# Tip_Tilt_Controller.net
KiCad netlist of a schematic drawn in EAGLE
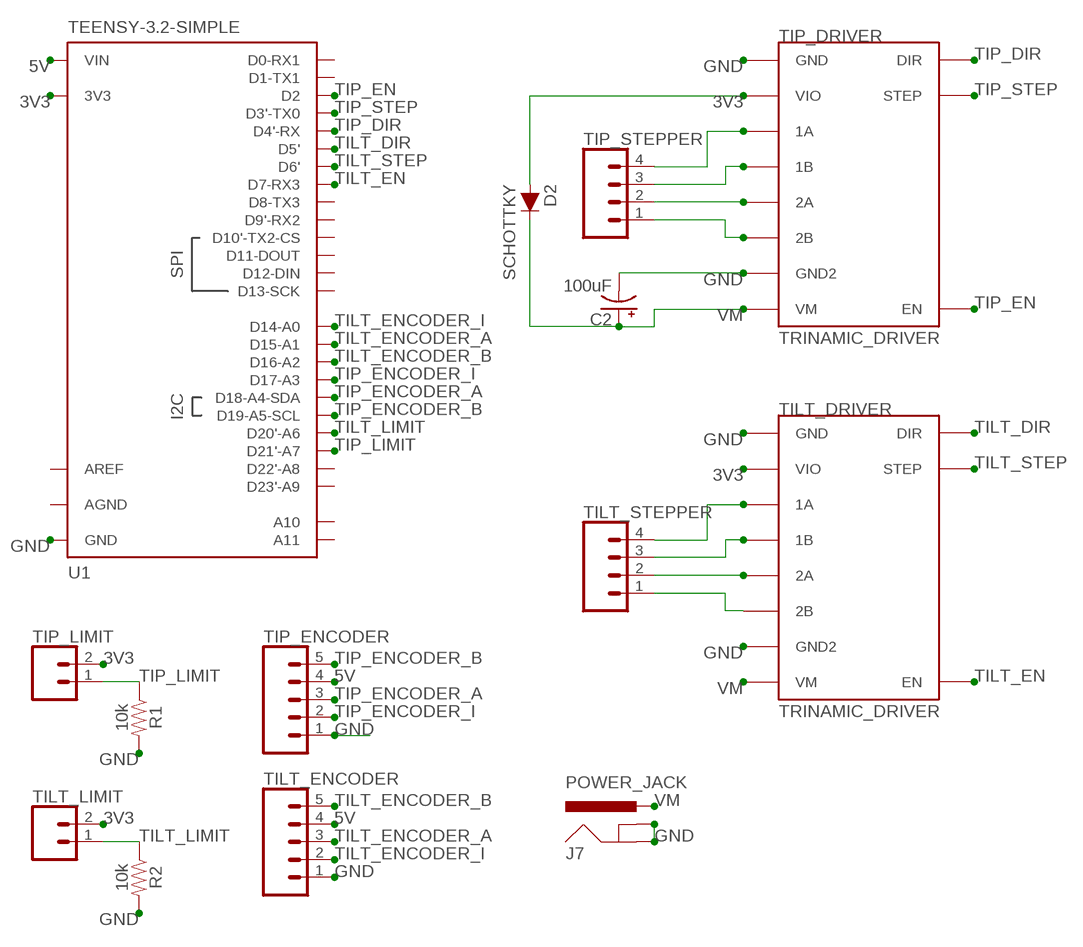
[diagram p0: schematic, sheet 1]

(export (version "E")
  (design (tool "Eeschema 10.0.6"))
  (components
    (comp (ref "C2")
      (value "100uF")
      (footprint "eagle-import:CPOL-RADIAL-2.5MM-6.5MM")
      (libsource (lib "eagle-import") (part "100UF-POLAR-RADIAL-2.5MM-25V-20%"))
    )
    (comp (ref "D2")
      (value "SCHOTTKY")
      (footprint "eagle-import:DIODE-1N4148")
      (libsource (lib "eagle-import") (part "DIODE-1N4148"))
    )
    (comp (ref "J7")
      (value "POWER_JACK")
      (footprint "eagle-import:POWER_JACK_PTH")
      (libsource (lib "eagle-import") (part "POWER_JACK"))
    )
    (comp (ref "R1")
      (value "10k")
      (footprint "eagle-import:AXIAL-0.3")
      (libsource (lib "eagle-import") (part "10KOHM-HORIZ-1/6W-5%"))
    )
    (comp (ref "R2")
      (value "10k")
      (footprint "eagle-import:AXIAL-0.3")
      (libsource (lib "eagle-import") (part "10KOHM-HORIZ-1/6W-5%"))
    )
    (comp (ref "TILT_DRIVER")
      (value "TRINAMIC_DRIVER")
      (footprint "eagle-import:TRINAMIC_DRIVER")
      (libsource (lib "eagle-import") (part "TRINAMIC_DRIVER"))
    )
    (comp (ref "TILT_ENCODER")
      (value "CONN_05")
      (footprint "eagle-import:1X05")
      (libsource (lib "eagle-import") (part "CONN_05"))
    )
    (comp (ref "TILT_LIMIT")
      (value "CONN_02")
      (footprint "eagle-import:1X02")
      (libsource (lib "eagle-import") (part "CONN_02"))
    )
    (comp (ref "TILT_STEPPER")
      (value "CONN_04PTH")
      (footprint "eagle-import:1X04")
      (libsource (lib "eagle-import") (part "CONN_04PTH"))
    )
    (comp (ref "TIP_DRIVER")
      (value "TRINAMIC_DRIVER")
      (footprint "eagle-import:TRINAMIC_DRIVER")
      (libsource (lib "eagle-import") (part "TRINAMIC_DRIVER"))
    )
    (comp (ref "TIP_ENCODER")
      (value "CONN_05")
      (footprint "eagle-import:1X05")
      (libsource (lib "eagle-import") (part "CONN_05"))
    )
    (comp (ref "TIP_LIMIT")
      (value "CONN_02")
      (footprint "eagle-import:1X02")
      (libsource (lib "eagle-import") (part "CONN_02"))
    )
    (comp (ref "TIP_STEPPER")
      (value "CONN_04PTH")
      (footprint "eagle-import:1X04")
      (libsource (lib "eagle-import") (part "CONN_04PTH"))
    )
    (comp (ref "U1")
      (value "TEENSY-3.2-SIMPLE")
      (footprint "eagle-import:TEENSY-3.2-SIMPLE")
      (libsource (lib "eagle-import") (part "TEENSY-3.2-SIMPLE"))
    )
  )
  (nets
    (net (code "1") (name "/3V3") (class "Default")
      (node (ref "D2") (pin "A") (pinfunction "A_A") (pintype "passive"))
      (node (ref "TILT_DRIVER") (pin "5V") (pinfunction "VIO_5V") (pintype "bidirectional"))
      (node (ref "TILT_LIMIT") (pin "2") (pinfunction "2_2") (pintype "passive"))
      (node (ref "TIP_DRIVER") (pin "5V") (pinfunction "VIO_5V") (pintype "bidirectional"))
      (node (ref "TIP_LIMIT") (pin "2") (pinfunction "2_2") (pintype "passive"))
      (node (ref "U1") (pin "3.3V") (pinfunction "3V3_3.3V") (pintype "power_in"))
    )
    (net (code "2") (name "/5V") (class "Default")
      (node (ref "TILT_ENCODER") (pin "4") (pinfunction "4_4") (pintype "passive"))
      (node (ref "TIP_ENCODER") (pin "4") (pinfunction "4_4") (pintype "passive"))
      (node (ref "U1") (pin "VIN") (pinfunction "VIN_VIN") (pintype "power_in"))
    )
    (net (code "3") (name "/AGND") (class "Default")
      (node (ref "U1") (pin "AGND") (pinfunction "AGND_AGND") (pintype "power_in"))
    )
    (net (code "4") (name "/AREF") (class "Default")
      (node (ref "U1") (pin "AREF") (pinfunction "AREF_AREF") (pintype "power_in"))
    )
    (net (code "5") (name "/GND") (class "Default")
      (node (ref "C2") (pin "2") (pinfunction "-_2") (pintype "passive"))
      (node (ref "J7") (pin "GND") (pinfunction "GND_GND") (pintype "bidirectional"))
      (node (ref "J7") (pin "GNDBREAK") (pinfunction "GNDBREAK_GNDBREAK") (pintype "bidirectional"))
      (node (ref "R1") (pin "P$2") (pinfunction "2_P$2") (pintype "passive"))
      (node (ref "R2") (pin "P$2") (pinfunction "2_P$2") (pintype "passive"))
      (node (ref "TILT_DRIVER") (pin "GND") (pinfunction "GND_GND") (pintype "bidirectional"))
      (node (ref "TILT_DRIVER") (pin "GND2") (pinfunction "GND2_GND2") (pintype "bidirectional"))
      (node (ref "TILT_ENCODER") (pin "1") (pinfunction "1_1") (pintype "passive"))
      (node (ref "TIP_DRIVER") (pin "GND") (pinfunction "GND_GND") (pintype "bidirectional"))
      (node (ref "TIP_DRIVER") (pin "GND2") (pinfunction "GND2_GND2") (pintype "bidirectional"))
      (node (ref "TIP_ENCODER") (pin "1") (pinfunction "1_1") (pintype "passive"))
      (node (ref "U1") (pin "GND") (pinfunction "GND_GND") (pintype "power_in"))
    )
    (net (code "6") (name "/TILT_DIR") (class "Default")
      (node (ref "TILT_DRIVER") (pin "DIR") (pinfunction "DIR_DIR") (pintype "bidirectional"))
      (node (ref "U1") (pin "5") (pinfunction "D5'_5") (pintype "bidirectional"))
    )
    (net (code "7") (name "/TILT_EN") (class "Default")
      (node (ref "TILT_DRIVER") (pin "EN") (pinfunction "EN_EN") (pintype "bidirectional"))
      (node (ref "U1") (pin "7") (pinfunction "D7-RX3_7") (pintype "bidirectional"))
    )
    (net (code "8") (name "/TILT_ENCODER_A") (class "Default")
      (node (ref "TILT_ENCODER") (pin "3") (pinfunction "3_3") (pintype "passive"))
      (node (ref "U1") (pin "15") (pinfunction "D15-A1_15") (pintype "bidirectional"))
    )
    (net (code "9") (name "/TILT_ENCODER_B") (class "Default")
      (node (ref "TILT_ENCODER") (pin "5") (pinfunction "5_5") (pintype "passive"))
      (node (ref "U1") (pin "16") (pinfunction "D16-A2_16") (pintype "bidirectional"))
    )
    (net (code "10") (name "/TILT_ENCODER_I") (class "Default")
      (node (ref "TILT_ENCODER") (pin "2") (pinfunction "2_2") (pintype "passive"))
      (node (ref "U1") (pin "14") (pinfunction "D14-A0_14") (pintype "bidirectional"))
    )
    (net (code "11") (name "/TILT_LIMIT") (class "Default")
      (node (ref "R2") (pin "P$1") (pinfunction "1_P$1") (pintype "passive"))
      (node (ref "TILT_LIMIT") (pin "1") (pinfunction "1_1") (pintype "passive"))
      (node (ref "U1") (pin "20") (pinfunction "D20'-A6_20") (pintype "bidirectional"))
    )
    (net (code "12") (name "/TILT_STEP") (class "Default")
      (node (ref "TILT_DRIVER") (pin "STEP") (pinfunction "STEP_STEP") (pintype "bidirectional"))
      (node (ref "U1") (pin "6") (pinfunction "D6'_6") (pintype "bidirectional"))
    )
    (net (code "13") (name "/TIP_DIR") (class "Default")
      (node (ref "TIP_DRIVER") (pin "DIR") (pinfunction "DIR_DIR") (pintype "bidirectional"))
      (node (ref "U1") (pin "4") (pinfunction "D4'-RX_4") (pintype "bidirectional"))
    )
    (net (code "14") (name "/TIP_EN") (class "Default")
      (node (ref "TIP_DRIVER") (pin "EN") (pinfunction "EN_EN") (pintype "bidirectional"))
      (node (ref "U1") (pin "2") (pinfunction "D2_2") (pintype "bidirectional"))
    )
    (net (code "15") (name "/TIP_ENCODER_A") (class "Default")
      (node (ref "TIP_ENCODER") (pin "3") (pinfunction "3_3") (pintype "passive"))
      (node (ref "U1") (pin "18") (pinfunction "D18-A4-SDA_18") (pintype "bidirectional"))
    )
    (net (code "16") (name "/TIP_ENCODER_B") (class "Default")
      (node (ref "TIP_ENCODER") (pin "5") (pinfunction "5_5") (pintype "passive"))
      (node (ref "U1") (pin "19") (pinfunction "D19-A5-SCL_19") (pintype "bidirectional"))
    )
    (net (code "17") (name "/TIP_ENCODER_I") (class "Default")
      (node (ref "TIP_ENCODER") (pin "2") (pinfunction "2_2") (pintype "passive"))
      (node (ref "U1") (pin "17") (pinfunction "D17-A3_17") (pintype "bidirectional"))
    )
    (net (code "18") (name "/TIP_LIMIT") (class "Default")
      (node (ref "R1") (pin "P$1") (pinfunction "1_P$1") (pintype "passive"))
      (node (ref "TIP_LIMIT") (pin "1") (pinfunction "1_1") (pintype "passive"))
      (node (ref "U1") (pin "21") (pinfunction "D21'-A7_21") (pintype "bidirectional"))
    )
    (net (code "19") (name "/TIP_STEP") (class "Default")
      (node (ref "TIP_DRIVER") (pin "STEP") (pinfunction "STEP_STEP") (pintype "bidirectional"))
      (node (ref "U1") (pin "3") (pinfunction "D3'-TX0_3") (pintype "bidirectional"))
    )
    (net (code "20") (name "/VM") (class "Default")
      (node (ref "C2") (pin "1") (pinfunction "+_1") (pintype "passive"))
      (node (ref "D2") (pin "C") (pinfunction "C_C") (pintype "passive"))
      (node (ref "J7") (pin "PWR") (pinfunction "PWR_PWR") (pintype "bidirectional"))
      (node (ref "TILT_DRIVER") (pin "VM") (pinfunction "VM_VM") (pintype "bidirectional"))
      (node (ref "TIP_DRIVER") (pin "VM") (pinfunction "VM_VM") (pintype "bidirectional"))
    )
    (net (code "21") (name "Net-(TILT_DRIVER-Pad1A)") (class "Default")
      (node (ref "TILT_DRIVER") (pin "1A") (pinfunction "1A_1A") (pintype "bidirectional"))
      (node (ref "TILT_STEPPER") (pin "4") (pinfunction "4_4") (pintype "passive"))
    )
    (net (code "22") (name "Net-(TILT_DRIVER-Pad1B)") (class "Default")
      (node (ref "TILT_DRIVER") (pin "1B") (pinfunction "1B_1B") (pintype "bidirectional"))
      (node (ref "TILT_STEPPER") (pin "3") (pinfunction "3_3") (pintype "passive"))
    )
    (net (code "23") (name "Net-(TILT_DRIVER-Pad2A)") (class "Default")
      (node (ref "TILT_DRIVER") (pin "2A") (pinfunction "2A_2A") (pintype "bidirectional"))
      (node (ref "TILT_STEPPER") (pin "2") (pinfunction "2_2") (pintype "passive"))
    )
    (net (code "24") (name "Net-(TILT_DRIVER-Pad2B)") (class "Default")
      (node (ref "TILT_DRIVER") (pin "2B") (pinfunction "2B_2B") (pintype "bidirectional"))
      (node (ref "TILT_STEPPER") (pin "1") (pinfunction "1_1") (pintype "passive"))
    )
    (net (code "25") (name "Net-(TIP_DRIVER-Pad1A)") (class "Default")
      (node (ref "TIP_DRIVER") (pin "1A") (pinfunction "1A_1A") (pintype "bidirectional"))
      (node (ref "TIP_STEPPER") (pin "4") (pinfunction "4_4") (pintype "passive"))
    )
    (net (code "26") (name "Net-(TIP_DRIVER-Pad1B)") (class "Default")
      (node (ref "TIP_DRIVER") (pin "1B") (pinfunction "1B_1B") (pintype "bidirectional"))
      (node (ref "TIP_STEPPER") (pin "3") (pinfunction "3_3") (pintype "passive"))
    )
    (net (code "27") (name "Net-(TIP_DRIVER-Pad2A)") (class "Default")
      (node (ref "TIP_DRIVER") (pin "2A") (pinfunction "2A_2A") (pintype "bidirectional"))
      (node (ref "TIP_STEPPER") (pin "2") (pinfunction "2_2") (pintype "passive"))
    )
    (net (code "28") (name "Net-(TIP_DRIVER-Pad2B)") (class "Default")
      (node (ref "TIP_DRIVER") (pin "2B") (pinfunction "2B_2B") (pintype "bidirectional"))
      (node (ref "TIP_STEPPER") (pin "1") (pinfunction "1_1") (pintype "passive"))
    )
    (net (code "29") (name "unconnected-(U1-D0-RX1-Pad0)") (class "Default")
      (node (ref "U1") (pin "0") (pinfunction "D0-RX1_0") (pintype "bidirectional"))
    )
    (net (code "30") (name "unconnected-(U1-D1-TX1-Pad1)") (class "Default")
      (node (ref "U1") (pin "1") (pinfunction "D1-TX1_1") (pintype "bidirectional"))
    )
    (net (code "31") (name "unconnected-(U1-D8-TX3-Pad8)") (class "Default")
      (node (ref "U1") (pin "8") (pinfunction "D8-TX3_8") (pintype "bidirectional"))
    )
    (net (code "32") (name "unconnected-(U1-D9'-RX2-Pad9)") (class "Default")
      (node (ref "U1") (pin "9") (pinfunction "D9'-RX2_9") (pintype "bidirectional"))
    )
    (net (code "33") (name "unconnected-(U1-D10'-TX2-CS-Pad10)") (class "Default")
      (node (ref "U1") (pin "10") (pinfunction "D10'-TX2-CS_10") (pintype "bidirectional"))
    )
    (net (code "34") (name "unconnected-(U1-D11-DOUT-Pad11)") (class "Default")
      (node (ref "U1") (pin "11") (pinfunction "D11-DOUT_11") (pintype "bidirectional"))
    )
    (net (code "35") (name "unconnected-(U1-D12-DIN-Pad12)") (class "Default")
      (node (ref "U1") (pin "12") (pinfunction "D12-DIN_12") (pintype "bidirectional"))
    )
    (net (code "36") (name "unconnected-(U1-D13-SCK-Pad13)") (class "Default")
      (node (ref "U1") (pin "13") (pinfunction "D13-SCK_13") (pintype "bidirectional"))
    )
    (net (code "37") (name "unconnected-(U1-D22'-A8-Pad22)") (class "Default")
      (node (ref "U1") (pin "22") (pinfunction "D22'-A8_22") (pintype "bidirectional"))
    )
    (net (code "38") (name "unconnected-(U1-D23'-A9-Pad23)") (class "Default")
      (node (ref "U1") (pin "23") (pinfunction "D23'-A9_23") (pintype "bidirectional"))
    )
    (net (code "39") (name "unconnected-(U1-PadA10)") (class "Default")
      (node (ref "U1") (pin "A10") (pinfunction "A10_A10") (pintype "bidirectional"))
    )
    (net (code "40") (name "unconnected-(U1-PadA11)") (class "Default")
      (node (ref "U1") (pin "A11") (pinfunction "A11_A11") (pintype "bidirectional"))
    )
  )
)
